# Measuring.net
KiCad netlist of a schematic drawn in Altium Designer
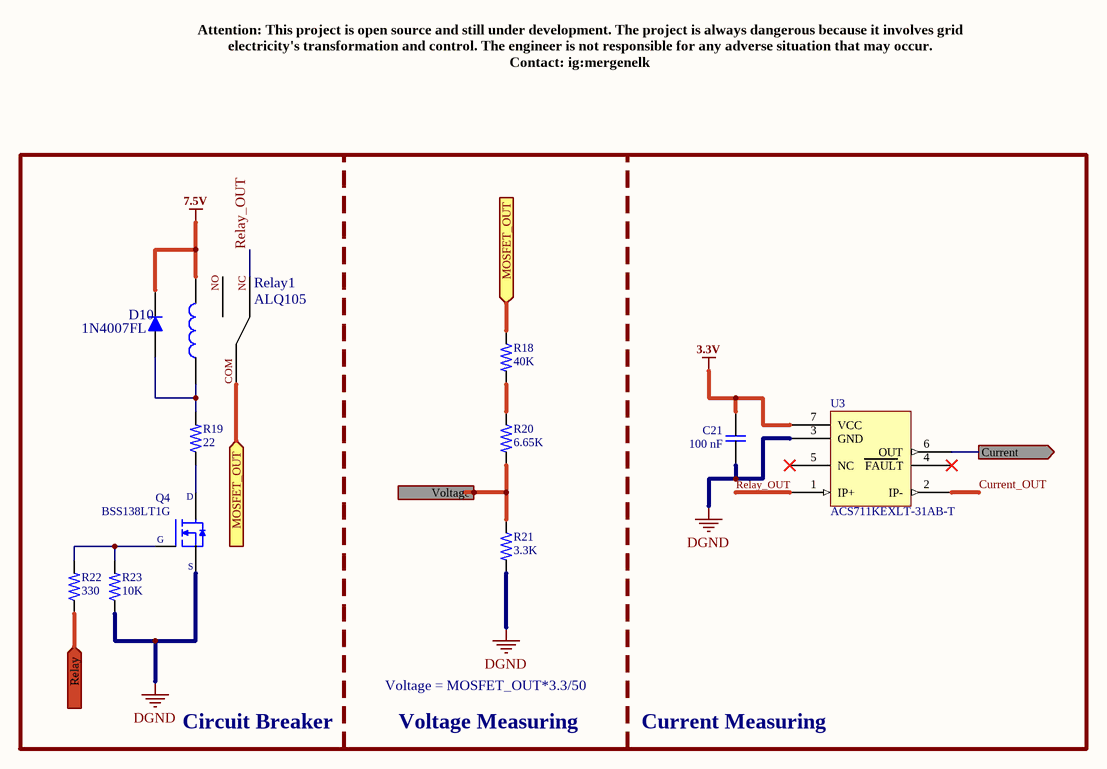
[diagram p0: Measuring.SchDoc]

(export (version "E")
  (design (tool "Eeschema 10.0.6"))
  (components
    (comp (ref "C21")
      (value "100 nF")
      (footprint "MergenElektronik_Capacitors_Ceramics_SMDs_0603_S_NS")
      (description "Mergen Elektronik - Capacitors - Ceramics - SMDs - 0603 - 100 nF - 16V")
      (fields (field (name "MANUFACTURER") "Samsung Electro-Mechanics") (field (name "TOLERANCE") "±10%"))
      (libsource (lib "MergenElektronik_Capacitors_Ceramics_SMDs") (part "MergenElektronik_Capacitors_Ceramic_SMDs_100nF_16V"))
    )
    (comp (ref "D10")
      (value "1N4007FL")
      (footprint "MergenElektronik_Diodes_SingleDiodes_SOD-123F")
      (description "Mergen Elektronik - Diodes - Single Diodes - 1N4007FL")
      (fields (field (name "MANUFACTURER") "SMC Diode Solutions"))
      (libsource (lib "MergenElektronik_Diodes_SingleDiodes") (part "MergenElektronik_Diodes_SingleDiodes_1N4007FL"))
    )
    (comp (ref "Q4")
      (value "BSS138LT1G")
      (footprint "MergenElektronik_Transistors_Mosfets_SOT-23")
      (description "Mergen Elektronik - Transistors - Mosfets - BSS138LT1G")
      (fields (field (name "MANUFACTURER") "onsemi"))
      (libsource (lib "MergenElektronik_Transistors_Mosfets") (part "MergenElektronik_Transistors_Mosfets_BSS138LT1G"))
    )
    (comp (ref "R18")
      (value "40K")
      (footprint "MergenElektronik_Resistors_ChipResistors_0603_S_NS")
      (description "Mergen Elektronik - Resistors - Chip Resistors - 0603 - 40K")
      (fields (field (name "MANUFACTURER") "YAGEO") (field (name "POWER") "1/10W"))
      (libsource (lib "MergenElektronik_Resistors_ChipResistors") (part "MergenElektronik_Resistors_ChipResistors_0603_40K"))
    )
    (comp (ref "R19")
      (value "22")
      (footprint "MergenElektronik_Resistors_ChipResistors_0603_S")
      (description "Mergen Elektronik - Resistors - Chip Resistors - 0603 - 22")
      (fields (field (name "MANUFACTURER") "TE Connectivity Passive Product") (field (name "POWER") "1/10W"))
      (libsource (lib "MergenElektronik_Resistors_ChipResistors") (part "MergenElektronik_Resistors_ChipResistors_0603_22"))
    )
    (comp (ref "R20")
      (value "6.65K")
      (footprint "MergenElektronik_Resistors_ChipResistors_0603_S_NS")
      (description "Mergen Elektronik - Resistors - Chip Resistors - 0603 - 6.65K")
      (fields (field (name "MANUFACTURER") "YAGEO") (field (name "POWER") "1/10W"))
      (libsource (lib "MergenElektronik_Resistors_ChipResistors") (part "MergenElektronik_Resistors_ChipResistors_0603_6.65K"))
    )
    (comp (ref "R21")
      (value "3.3K")
      (footprint "MergenElektronik_Resistors_ChipResistors_0603_S_NS")
      (description "Mergen Elektronik - Resistors - Chip Resistors - 0603 - 3.3K")
      (fields (field (name "MANUFACTURER") "YAGEO") (field (name "POWER") "1/10W"))
      (libsource (lib "MergenElektronik_Resistors_ChipResistors") (part "MergenElektronik_Resistors_ChipResistors_0603_3.3K"))
    )
    (comp (ref "R22")
      (value "330")
      (footprint "MergenElektronik_Resistors_ChipResistors_0603_S_NS")
      (description "Mergen Elektronik - Resistors - Chip Resistors - 0603 - 330R")
      (fields (field (name "MANUFACTURER") "Stackpole Electronics Inc") (field (name "POWER") "1/10W"))
      (libsource (lib "MergenElektronik_Resistors_ChipResistors") (part "MergenElektronik_Resistors_ChipResistors_0603_330R"))
    )
    (comp (ref "R23")
      (value "10K")
      (footprint "MergenElektronik_Resistors_ChipResistors_0603_S_NS")
      (description "Mergen Elektronik - Resistors - Chip Resistors - 0603 - 10K")
      (fields (field (name "MANUFACTURER") "Stackpole Electronics Inc") (field (name "POWER") "1/10W"))
      (libsource (lib "MergenElektronik_Resistors_ChipResistors") (part "MergenElektronik_Resistors_ChipResistors_0603_10K"))
    )
    (comp (ref "Relay1")
      (value "ALQ105")
      (footprint "MergenElektronik_Relays_PowerRelays_ALQ105")
      (description "Mergen Elektronik - Relays - Power Relays - ALQ105")
      (fields (field (name "MANUFACTURER") "Panasonic Electric Works"))
      (libsource (lib "MergenElektronik_Relays_PowerRelays") (part "MergenElektronik_Relays_PowerRelays_ALQ105"))
    )
    (comp (ref "U3")
      (value "ACS711KEXLT-31AB-T")
      (footprint "MergenElektronik_Sensors_CurrentSensors_ACS711KEXLT-31AB-T")
      (description "Mergen Elektronik - Sensors - Current Sensors - ACS711KEXLT-31AB-T")
      (fields (field (name "MANUFACTURER") "Allegro MicroSystems"))
      (libsource (lib "MergenElektronik_Sensors_CurrentSensors") (part "MergenElektronik_Sensors_CurrentSensors_ACS711KEXLT-31AB-T"))
    )
  )
  (nets
    (net (code "1") (name "/Current") (class "Default")
      (node (ref "U3") (pin "6") (pinfunction "OUT_6") (pintype "output"))
    )
    (net (code "2") (name "/Current_OUT") (class "Default")
      (node (ref "U3") (pin "2") (pinfunction "IP-_2") (pintype "output"))
    )
    (net (code "3") (name "/MOSFET_OUT") (class "Default")
      (node (ref "R18") (pin "1") (pinfunction "1_1") (pintype "passive"))
      (node (ref "Relay1") (pin "COM") (pinfunction "COM_COM") (pintype "passive"))
    )
    (net (code "4") (name "/Relay") (class "Default")
      (node (ref "R22") (pin "1") (pinfunction "1_1") (pintype "passive"))
    )
    (net (code "5") (name "/Relay_OUT") (class "Default")
      (node (ref "Relay1") (pin "NC") (pinfunction "NC_NC") (pintype "passive"))
      (node (ref "U3") (pin "1") (pinfunction "IP+_1") (pintype "input"))
    )
    (net (code "6") (name "/Voltage") (class "Default")
      (node (ref "R20") (pin "2") (pinfunction "2_2") (pintype "passive"))
      (node (ref "R21") (pin "1") (pinfunction "1_1") (pintype "passive"))
    )
    (net (code "7") (name "3.3V") (class "Default")
      (node (ref "C21") (pin "1") (pinfunction "1_1") (pintype "passive"))
      (node (ref "U3") (pin "7") (pinfunction "VCC_7") (pintype "power_in"))
    )
    (net (code "8") (name "7.5V") (class "Default")
      (node (ref "D10") (pin "2") (pinfunction "KATOT_2") (pintype "passive"))
      (node (ref "Relay1") (pin "C2") (pinfunction "C2_C2") (pintype "passive"))
    )
    (net (code "9") (name "DGND") (class "Default")
      (node (ref "C21") (pin "2") (pinfunction "2_2") (pintype "passive"))
      (node (ref "Q4") (pin "2") (pinfunction "Source_2") (pintype "passive"))
      (node (ref "R21") (pin "2") (pinfunction "2_2") (pintype "passive"))
      (node (ref "R23") (pin "1") (pinfunction "1_1") (pintype "passive"))
      (node (ref "U3") (pin "3") (pinfunction "GND_3") (pintype "power_in"))
    )
    (net (code "10") (name "Net-(D10-ANOT)") (class "Default")
      (node (ref "D10") (pin "1") (pinfunction "ANOT_1") (pintype "passive"))
      (node (ref "R19") (pin "2") (pinfunction "2_2") (pintype "passive"))
      (node (ref "Relay1") (pin "C1") (pinfunction "C1_C1") (pintype "passive"))
    )
    (net (code "11") (name "Net-(Q4-Drain)") (class "Default")
      (node (ref "Q4") (pin "3") (pinfunction "Drain_3") (pintype "passive"))
      (node (ref "R19") (pin "1") (pinfunction "1_1") (pintype "passive"))
    )
    (net (code "12") (name "Net-(Q4-Gate)") (class "Default")
      (node (ref "Q4") (pin "1") (pinfunction "Gate_1") (pintype "passive"))
      (node (ref "R22") (pin "2") (pinfunction "2_2") (pintype "passive"))
      (node (ref "R23") (pin "2") (pinfunction "2_2") (pintype "passive"))
    )
    (net (code "13") (name "Net-(R18-Pad2)") (class "Default")
      (node (ref "R18") (pin "2") (pinfunction "2_2") (pintype "passive"))
      (node (ref "R20") (pin "1") (pinfunction "1_1") (pintype "passive"))
    )
    (net (code "14") (name "unconnected-(Relay1-PadNO)") (class "Default")
      (node (ref "Relay1") (pin "NO") (pinfunction "NO_NO") (pintype "passive"))
    )
    (net (code "15") (name "unconnected-(U3-FAULT-Pad4)") (class "Default")
      (node (ref "U3") (pin "4") (pinfunction "FAULT_4") (pintype "passive+no_connect"))
    )
    (net (code "16") (name "unconnected-(U3-NC-Pad5)") (class "Default")
      (node (ref "U3") (pin "5") (pinfunction "NC_5") (pintype "passive+no_connect"))
    )
  )
)
